# HenrySchem.net
KiCad netlist of a schematic drawn in EAGLE
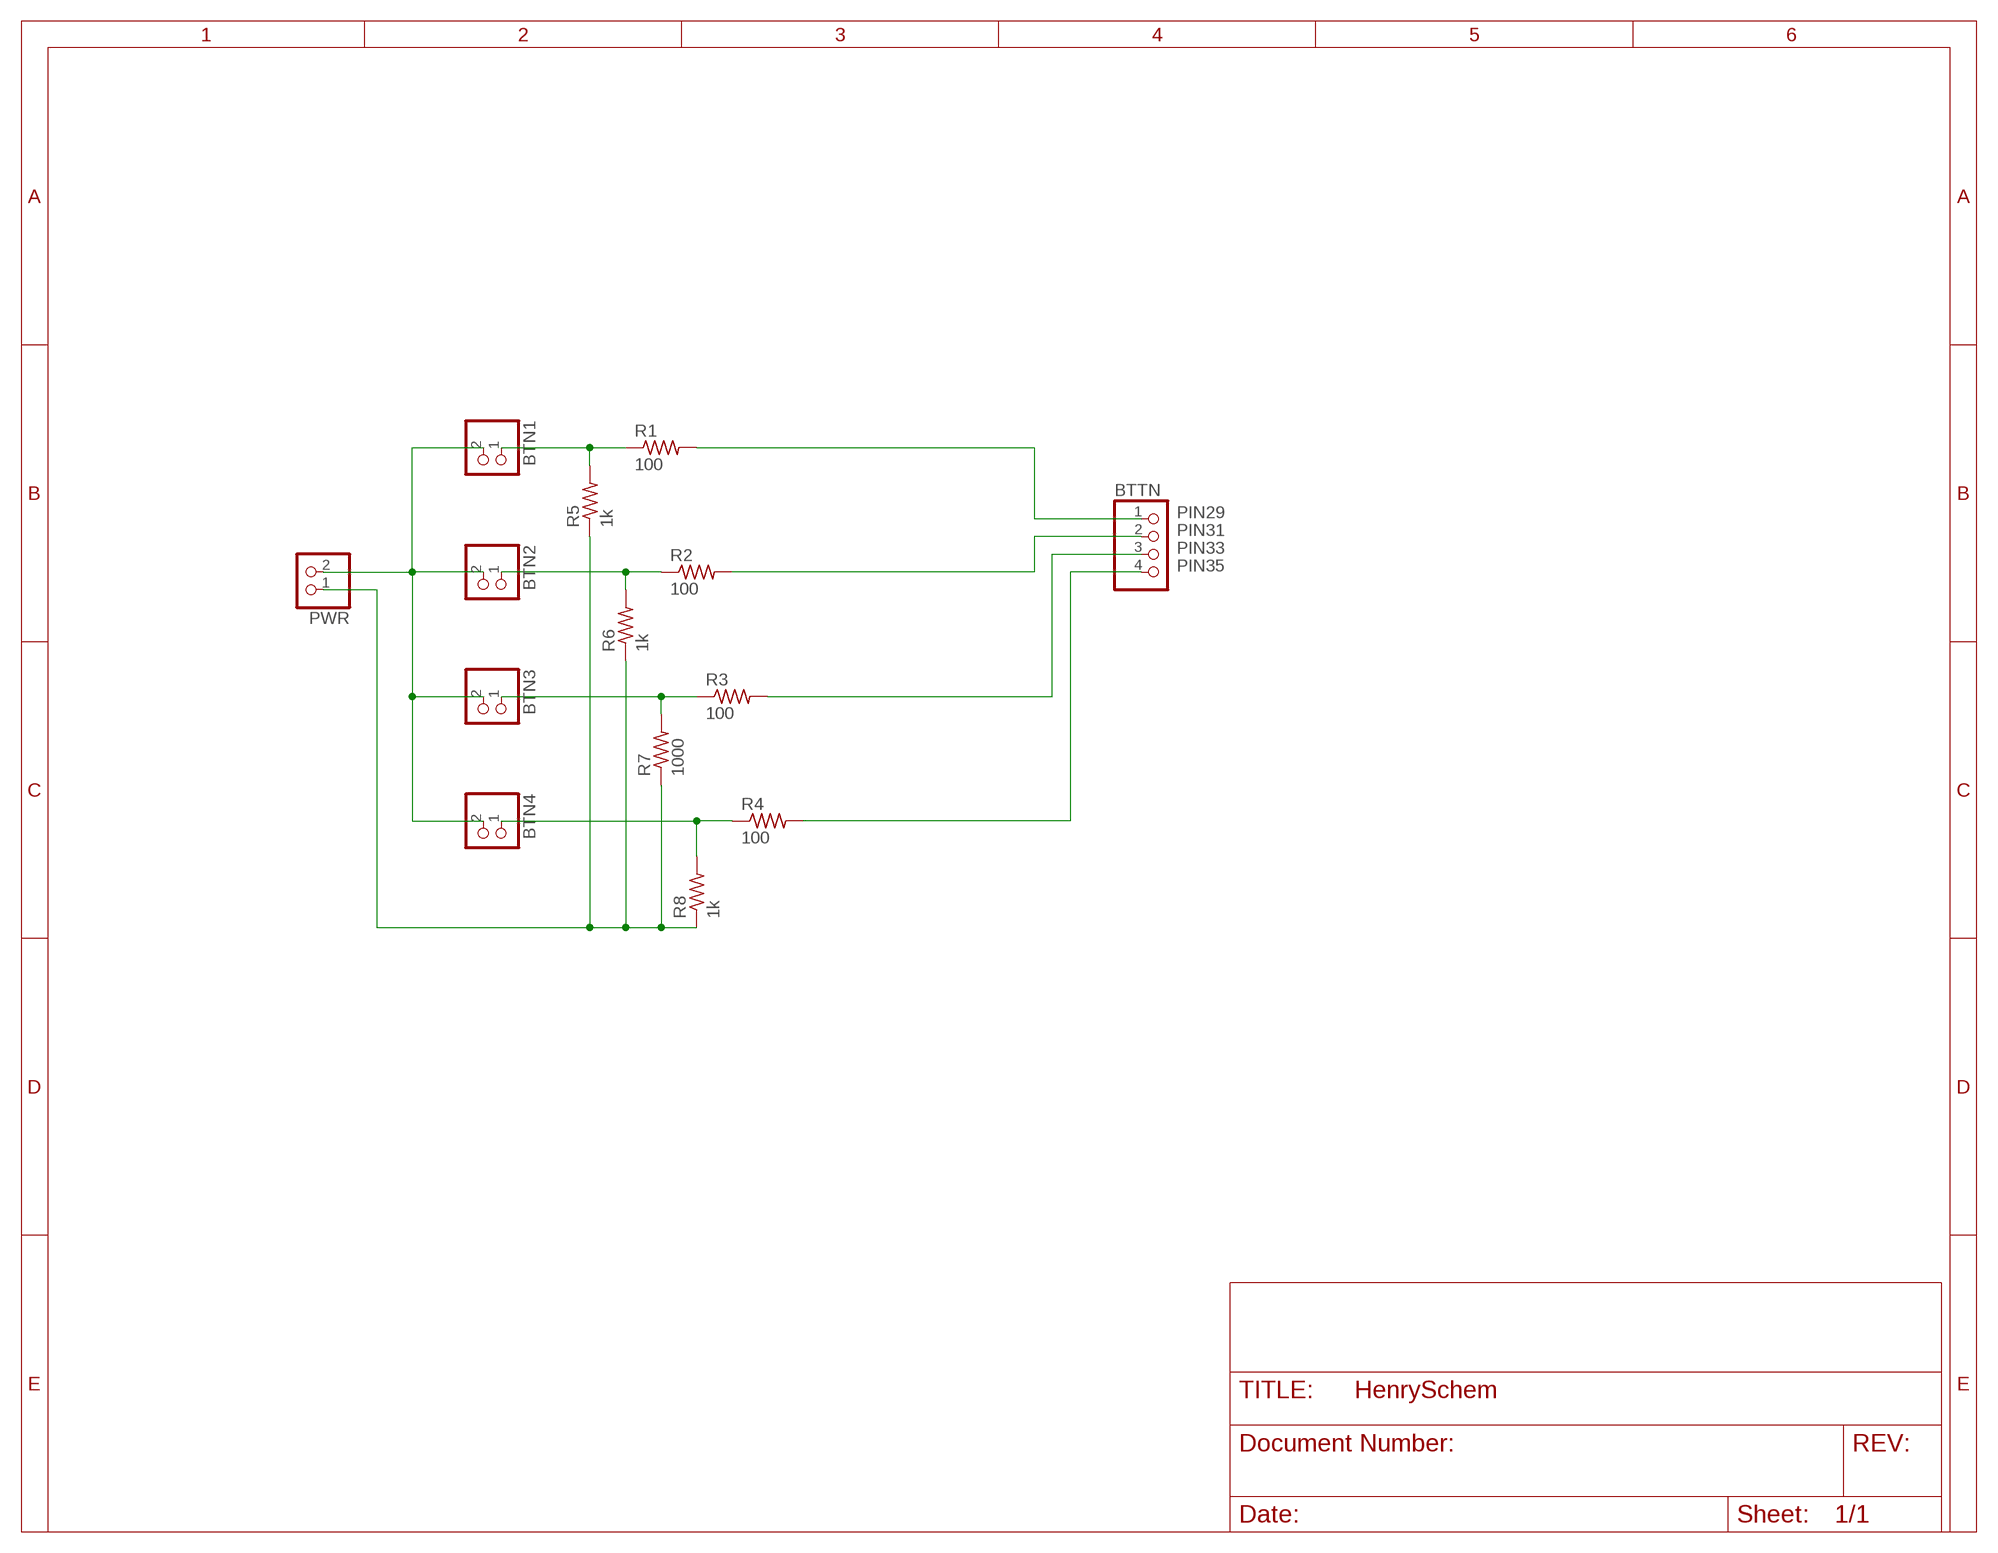
[diagram p0: schematic, sheet 1]

(export (version "E")
  (design (tool "Eeschema 10.0.6"))
  (components
    (comp (ref "BTN1")
      (value "PINHD-1X2")
      (footprint "eagle-import:1X02")
      (libsource (lib "eagle-import") (part "PINHD-1X2"))
    )
    (comp (ref "BTN2")
      (value "PINHD-1X2")
      (footprint "eagle-import:1X02")
      (libsource (lib "eagle-import") (part "PINHD-1X2"))
    )
    (comp (ref "BTN3")
      (value "PINHD-1X2")
      (footprint "eagle-import:1X02")
      (libsource (lib "eagle-import") (part "PINHD-1X2"))
    )
    (comp (ref "BTN4")
      (value "PINHD-1X2")
      (footprint "eagle-import:1X02")
      (libsource (lib "eagle-import") (part "PINHD-1X2"))
    )
    (comp (ref "BTTN")
      (value "PINHD-1X4")
      (footprint "eagle-import:1X04")
      (libsource (lib "eagle-import") (part "PINHD-1X4"))
    )
    (comp (ref "PWR")
      (value "PINHD-1X2")
      (footprint "eagle-import:1X02")
      (libsource (lib "eagle-import") (part "PINHD-1X2"))
    )
    (comp (ref "R1")
      (value "100")
      (footprint "eagle-import:0204_5")
      (libsource (lib "eagle-import") (part "R-US_0204/5"))
    )
    (comp (ref "R2")
      (value "100")
      (footprint "eagle-import:0204_5")
      (libsource (lib "eagle-import") (part "R-US_0204/5"))
    )
    (comp (ref "R3")
      (value "100")
      (footprint "eagle-import:0204_5")
      (libsource (lib "eagle-import") (part "R-US_0204/5"))
    )
    (comp (ref "R4")
      (value "100")
      (footprint "eagle-import:0204_5")
      (libsource (lib "eagle-import") (part "R-US_0204/5"))
    )
    (comp (ref "R5")
      (value "1k")
      (footprint "eagle-import:0204_5")
      (libsource (lib "eagle-import") (part "R-US_0204/5"))
    )
    (comp (ref "R6")
      (value "1k")
      (footprint "eagle-import:0204_5")
      (libsource (lib "eagle-import") (part "R-US_0204/5"))
    )
    (comp (ref "R7")
      (value "1000")
      (footprint "eagle-import:0204_5")
      (libsource (lib "eagle-import") (part "R-US_0204/5"))
    )
    (comp (ref "R8")
      (value "1k")
      (footprint "eagle-import:0204_5")
      (libsource (lib "eagle-import") (part "R-US_0204/5"))
    )
  )
  (nets
    (net (code "1") (name "/PIN29") (class "Default")
      (node (ref "BTTN") (pin "1") (pinfunction "1_1") (pintype "passive"))
      (node (ref "R1") (pin "2") (pinfunction "2_2") (pintype "passive"))
    )
    (net (code "2") (name "/PIN31") (class "Default")
      (node (ref "BTTN") (pin "2") (pinfunction "2_2") (pintype "passive"))
      (node (ref "R2") (pin "2") (pinfunction "2_2") (pintype "passive"))
    )
    (net (code "3") (name "/PIN33") (class "Default")
      (node (ref "BTTN") (pin "3") (pinfunction "3_3") (pintype "passive"))
      (node (ref "R3") (pin "2") (pinfunction "2_2") (pintype "passive"))
    )
    (net (code "4") (name "/PIN35") (class "Default")
      (node (ref "BTTN") (pin "4") (pinfunction "4_4") (pintype "passive"))
      (node (ref "R4") (pin "2") (pinfunction "2_2") (pintype "passive"))
    )
    (net (code "5") (name "Net-(BTN1-Pad1)") (class "Default")
      (node (ref "BTN1") (pin "1") (pinfunction "1_1") (pintype "passive"))
      (node (ref "R1") (pin "1") (pinfunction "1_1") (pintype "passive"))
      (node (ref "R5") (pin "2") (pinfunction "2_2") (pintype "passive"))
    )
    (net (code "6") (name "Net-(BTN1-Pad2)") (class "Default")
      (node (ref "BTN1") (pin "2") (pinfunction "2_2") (pintype "passive"))
      (node (ref "BTN2") (pin "2") (pinfunction "2_2") (pintype "passive"))
      (node (ref "BTN3") (pin "2") (pinfunction "2_2") (pintype "passive"))
      (node (ref "BTN4") (pin "2") (pinfunction "2_2") (pintype "passive"))
      (node (ref "PWR") (pin "2") (pinfunction "2_2") (pintype "passive"))
    )
    (net (code "7") (name "Net-(BTN2-Pad1)") (class "Default")
      (node (ref "BTN2") (pin "1") (pinfunction "1_1") (pintype "passive"))
      (node (ref "R2") (pin "1") (pinfunction "1_1") (pintype "passive"))
      (node (ref "R6") (pin "2") (pinfunction "2_2") (pintype "passive"))
    )
    (net (code "8") (name "Net-(BTN3-Pad1)") (class "Default")
      (node (ref "BTN3") (pin "1") (pinfunction "1_1") (pintype "passive"))
      (node (ref "R3") (pin "1") (pinfunction "1_1") (pintype "passive"))
      (node (ref "R7") (pin "2") (pinfunction "2_2") (pintype "passive"))
    )
    (net (code "9") (name "Net-(BTN4-Pad1)") (class "Default")
      (node (ref "BTN4") (pin "1") (pinfunction "1_1") (pintype "passive"))
      (node (ref "R4") (pin "1") (pinfunction "1_1") (pintype "passive"))
      (node (ref "R8") (pin "2") (pinfunction "2_2") (pintype "passive"))
    )
    (net (code "10") (name "Net-(PWR-Pad1)") (class "Default")
      (node (ref "PWR") (pin "1") (pinfunction "1_1") (pintype "passive"))
      (node (ref "R5") (pin "1") (pinfunction "1_1") (pintype "passive"))
      (node (ref "R6") (pin "1") (pinfunction "1_1") (pintype "passive"))
      (node (ref "R7") (pin "1") (pinfunction "1_1") (pintype "passive"))
      (node (ref "R8") (pin "1") (pinfunction "1_1") (pintype "passive"))
    )
  )
)
